# xiqiu.net
KiCad netlist of a schematic drawn in Altium Designer
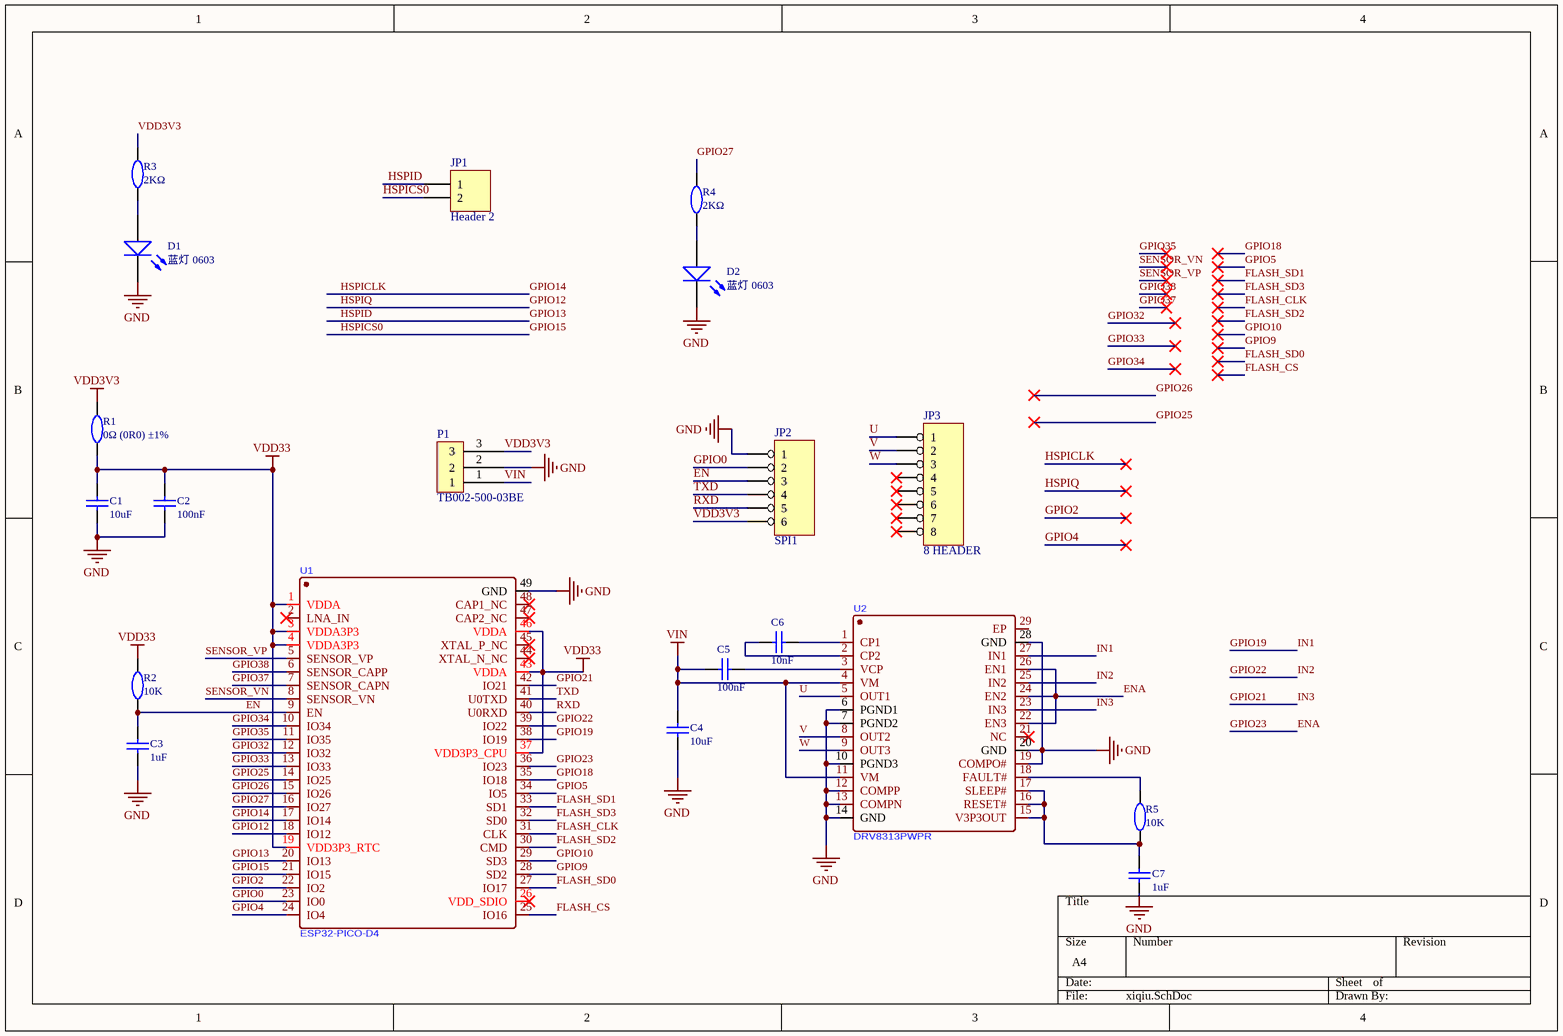
[diagram p0: xiqiu.SchDoc]

(export (version "E")
  (design (tool "Eeschema 10.0.6"))
  (components
    (comp (ref "C1")
      (value "10uF")
      (footprint "0603C")
      (libsource (lib "altium-import") (part "root_1_10uF_"))
    )
    (comp (ref "C2")
      (value "100nF")
      (footprint "0603C")
      (libsource (lib "altium-import") (part "root_1_100nF_"))
    )
    (comp (ref "C3") (value "1uF") (footprint "0603C") (libsource (lib "altium-import") (part "root_1_1uF_")))
    (comp (ref "C4")
      (value "10uF")
      (footprint "0603C")
      (libsource (lib "altium-import") (part "root_1_10uF_"))
    )
    (comp (ref "C5")
      (value "100nF")
      (footprint "0603C")
      (libsource (lib "altium-import") (part "root_2_100nF_"))
    )
    (comp (ref "C6")
      (value "10nF")
      (footprint "0603C")
      (libsource (lib "altium-import") (part "root_0_10nF_"))
    )
    (comp (ref "C7") (value "1uF") (footprint "0603C") (libsource (lib "altium-import") (part "root_1_1uF_")))
    (comp (ref "D1")
      (value "蓝灯 0603")
      (footprint "0603_diode")
      (libsource (lib "altium-import") (part "root_3_蓝灯 0603_"))
    )
    (comp (ref "D2")
      (value "蓝灯 0603")
      (footprint "0603_diode")
      (libsource (lib "altium-import") (part "root_3_蓝灯 0603_"))
    )
    (comp (ref "JP1")
      (value "Header 2")
      (footprint "SHDR2")
      (description "Header, 2-Pin")
      (fields (field (name "PUBLISHER") "Altium Limited"))
      (libsource (lib "Miscellaneous Connectors") (part "Header 2"))
    )
    (comp (ref "JP2") (value "SPI1") (footprint "SHDR6") (libsource (lib "刘涛20200314") (part "HEADER 6")))
    (comp (ref "JP3")
      (value "8 HEADER")
      (footprint "8P - WF25122")
      (description "8 Pin Header")
      (libsource (lib "刘涛20200314") (part "8 HEADER"))
    )
    (comp (ref "P1")
      (value "TB002-500-03BE")
      (footprint "SHDR3")
      (libsource (lib "ArduinoFOC") (part "TB002-500-03BE"))
    )
    (comp (ref "R1")
      (value "0Ω (0R0) ±1%")
      (footprint "0603")
      (libsource (lib "altium-import") (part "root_1_0Ω (0R0) ±1%_"))
    )
    (comp (ref "R2") (value "10K") (footprint "0603R") (libsource (lib "altium-import") (part "root_1_10K_")))
    (comp (ref "R3") (value "2KΩ") (footprint "0603") (libsource (lib "altium-import") (part "root_1_2KΩ_")))
    (comp (ref "R4") (value "2KΩ") (footprint "0603") (libsource (lib "altium-import") (part "root_1_2KΩ_")))
    (comp (ref "R5") (value "10K") (footprint "0603R") (libsource (lib "altium-import") (part "root_1_10K_")))
    (comp (ref "U1")
      (value "ESP32-PICO-D4")
      (footprint "pico")
      (libsource (lib "altium-import") (part "root_0_ESP32-PICO-D4_"))
    )
    (comp (ref "U2")
      (value "DRV8313PWPR")
      (footprint "HTSSOP-28_L9.8-W4.5-P0.65-LS6.6-BL-EP")
      (libsource (lib "altium-import") (part "root_0_DRV8313PWPR_"))
    )
  )
  (nets
    (net (code "1") (name "/EN") (class "Default")
      (node (ref "C3") (pin "2") (pinfunction "2_2") (pintype "passive"))
      (node (ref "JP2") (pin "3") (pinfunction "3_3") (pintype "passive"))
      (node (ref "R2") (pin "1") (pinfunction "1_1") (pintype "passive"))
      (node (ref "U1") (pin "9") (pinfunction "EN_9") (pintype "passive"))
    )
    (net (code "2") (name "/ENA") (class "Default")
      (node (ref "U1") (pin "36") (pinfunction "IO23_36") (pintype "passive"))
      (node (ref "U2") (pin "22") (pinfunction "EN3_22") (pintype "passive"))
      (node (ref "U2") (pin "24") (pinfunction "EN2_24") (pintype "passive"))
      (node (ref "U2") (pin "26") (pinfunction "EN1_26") (pintype "passive"))
    )
    (net (code "3") (name "/FLASH_CLK") (class "Default")
      (node (ref "U1") (pin "31") (pinfunction "CLK_31") (pintype "passive"))
    )
    (net (code "4") (name "/FLASH_CS") (class "Default")
      (node (ref "U1") (pin "25") (pinfunction "IO16_25") (pintype "passive"))
    )
    (net (code "5") (name "/FLASH_SD0") (class "Default")
      (node (ref "U1") (pin "27") (pinfunction "IO17_27") (pintype "passive"))
    )
    (net (code "6") (name "/FLASH_SD1") (class "Default")
      (node (ref "U1") (pin "33") (pinfunction "SD1_33") (pintype "passive"))
    )
    (net (code "7") (name "/FLASH_SD2") (class "Default")
      (node (ref "U1") (pin "30") (pinfunction "CMD_30") (pintype "passive"))
    )
    (net (code "8") (name "/FLASH_SD3") (class "Default")
      (node (ref "U1") (pin "32") (pinfunction "SD0_32") (pintype "passive"))
    )
    (net (code "9") (name "/GPIO0") (class "Default")
      (node (ref "JP2") (pin "2") (pinfunction "2_2") (pintype "passive"))
      (node (ref "U1") (pin "23") (pinfunction "IO0_23") (pintype "passive"))
    )
    (net (code "10") (name "/GPIO2") (class "Default")
      (node (ref "U1") (pin "22") (pinfunction "IO2_22") (pintype "passive"))
    )
    (net (code "11") (name "/GPIO4") (class "Default")
      (node (ref "U1") (pin "24") (pinfunction "IO4_24") (pintype "passive"))
    )
    (net (code "12") (name "/GPIO5") (class "Default")
      (node (ref "U1") (pin "34") (pinfunction "IO5_34") (pintype "passive"))
    )
    (net (code "13") (name "/GPIO9") (class "Default")
      (node (ref "U1") (pin "28") (pinfunction "SD2_28") (pintype "passive"))
    )
    (net (code "14") (name "/GPIO10") (class "Default")
      (node (ref "U1") (pin "29") (pinfunction "SD3_29") (pintype "passive"))
    )
    (net (code "15") (name "/GPIO12") (class "Default")
      (node (ref "U1") (pin "18") (pinfunction "IO12_18") (pintype "passive"))
    )
    (net (code "16") (name "/GPIO13") (class "Default")
      (node (ref "JP1") (pin "2") (pinfunction "1_2") (pintype "passive"))
      (node (ref "U1") (pin "20") (pinfunction "IO13_20") (pintype "passive"))
    )
    (net (code "17") (name "/GPIO14") (class "Default")
      (node (ref "U1") (pin "17") (pinfunction "IO14_17") (pintype "passive"))
    )
    (net (code "18") (name "/GPIO15") (class "Default")
      (node (ref "JP1") (pin "1") (pinfunction "2_1") (pintype "passive"))
      (node (ref "U1") (pin "21") (pinfunction "IO15_21") (pintype "passive"))
    )
    (net (code "19") (name "/GPIO18") (class "Default")
      (node (ref "U1") (pin "35") (pinfunction "IO18_35") (pintype "passive"))
    )
    (net (code "20") (name "/GPIO19") (class "Default")
      (node (ref "U1") (pin "38") (pinfunction "IO19_38") (pintype "passive"))
      (node (ref "U2") (pin "27") (pinfunction "IN1_27") (pintype "passive"))
    )
    (net (code "21") (name "/GPIO21") (class "Default")
      (node (ref "U1") (pin "42") (pinfunction "IO21_42") (pintype "passive"))
      (node (ref "U2") (pin "23") (pinfunction "IN3_23") (pintype "passive"))
    )
    (net (code "22") (name "/GPIO22") (class "Default")
      (node (ref "U1") (pin "39") (pinfunction "IO22_39") (pintype "passive"))
      (node (ref "U2") (pin "25") (pinfunction "IN2_25") (pintype "passive"))
    )
    (net (code "23") (name "/GPIO25") (class "Default")
      (node (ref "U1") (pin "14") (pinfunction "IO25_14") (pintype "passive"))
    )
    (net (code "24") (name "/GPIO26") (class "Default")
      (node (ref "U1") (pin "15") (pinfunction "IO26_15") (pintype "passive"))
    )
    (net (code "25") (name "/GPIO27") (class "Default")
      (node (ref "R4") (pin "2") (pinfunction "2_2") (pintype "passive"))
      (node (ref "U1") (pin "16") (pinfunction "IO27_16") (pintype "passive"))
    )
    (net (code "26") (name "/GPIO32") (class "Default")
      (node (ref "U1") (pin "12") (pinfunction "IO32_12") (pintype "passive"))
    )
    (net (code "27") (name "/GPIO33") (class "Default")
      (node (ref "U1") (pin "13") (pinfunction "IO33_13") (pintype "passive"))
    )
    (net (code "28") (name "/GPIO34") (class "Default")
      (node (ref "U1") (pin "10") (pinfunction "IO34_10") (pintype "passive"))
    )
    (net (code "29") (name "/GPIO35") (class "Default")
      (node (ref "U1") (pin "11") (pinfunction "IO35_11") (pintype "passive"))
    )
    (net (code "30") (name "/GPIO37") (class "Default")
      (node (ref "U1") (pin "7") (pinfunction "SENSOR_CAPN_7") (pintype "passive"))
    )
    (net (code "31") (name "/GPIO38") (class "Default")
      (node (ref "U1") (pin "6") (pinfunction "SENSOR_CAPP_6") (pintype "passive"))
    )
    (net (code "32") (name "/RXD") (class "Default")
      (node (ref "JP2") (pin "5") (pinfunction "5_5") (pintype "passive"))
      (node (ref "U1") (pin "40") (pinfunction "U0RXD_40") (pintype "passive"))
    )
    (net (code "33") (name "/SENSOR_VN") (class "Default")
      (node (ref "U1") (pin "8") (pinfunction "SENSOR_VN_8") (pintype "passive"))
    )
    (net (code "34") (name "/SENSOR_VP") (class "Default")
      (node (ref "U1") (pin "5") (pinfunction "SENSOR_VP_5") (pintype "passive"))
    )
    (net (code "35") (name "/TXD") (class "Default")
      (node (ref "JP2") (pin "4") (pinfunction "4_4") (pintype "passive"))
      (node (ref "U1") (pin "41") (pinfunction "U0TXD_41") (pintype "passive"))
    )
    (net (code "36") (name "/U") (class "Default")
      (node (ref "JP3") (pin "1") (pinfunction "1_1") (pintype "passive"))
      (node (ref "U2") (pin "5") (pinfunction "OUT1_5") (pintype "passive"))
    )
    (net (code "37") (name "/V") (class "Default")
      (node (ref "JP3") (pin "2") (pinfunction "2_2") (pintype "passive"))
      (node (ref "U2") (pin "8") (pinfunction "OUT2_8") (pintype "passive"))
    )
    (net (code "38") (name "/W") (class "Default")
      (node (ref "JP3") (pin "3") (pinfunction "3_3") (pintype "passive"))
      (node (ref "U2") (pin "9") (pinfunction "OUT3_9") (pintype "passive"))
    )
    (net (code "39") (name "GND") (class "Default")
      (node (ref "C1") (pin "1") (pinfunction "1_1") (pintype "passive"))
      (node (ref "C2") (pin "1") (pinfunction "1_1") (pintype "passive"))
      (node (ref "C3") (pin "1") (pinfunction "1_1") (pintype "passive"))
      (node (ref "C4") (pin "1") (pinfunction "1_1") (pintype "passive"))
      (node (ref "C7") (pin "1") (pinfunction "1_1") (pintype "passive"))
      (node (ref "D1") (pin "K") (pinfunction "K_K") (pintype "passive"))
      (node (ref "D2") (pin "K") (pinfunction "K_K") (pintype "passive"))
      (node (ref "JP2") (pin "1") (pinfunction "1_1") (pintype "passive"))
      (node (ref "P1") (pin "2") (pinfunction "2_2") (pintype "passive"))
      (node (ref "U1") (pin "49") (pinfunction "GND_49") (pintype "passive"))
      (node (ref "U2") (pin "10") (pinfunction "PGND3_10") (pintype "passive"))
      (node (ref "U2") (pin "12") (pinfunction "COMPP_12") (pintype "passive"))
      (node (ref "U2") (pin "13") (pinfunction "COMPN_13") (pintype "passive"))
      (node (ref "U2") (pin "14") (pinfunction "GND_14") (pintype "passive"))
      (node (ref "U2") (pin "19") (pinfunction "COMPO#_19") (pintype "passive"))
      (node (ref "U2") (pin "20") (pinfunction "GND_20") (pintype "passive"))
      (node (ref "U2") (pin "28") (pinfunction "GND_28") (pintype "passive"))
      (node (ref "U2") (pin "6") (pinfunction "PGND1_6") (pintype "passive"))
      (node (ref "U2") (pin "7") (pinfunction "PGND2_7") (pintype "passive"))
    )
    (net (code "40") (name "Net-(D1-PadA)") (class "Default")
      (node (ref "D1") (pin "A") (pinfunction "A_A") (pintype "passive"))
      (node (ref "R3") (pin "1") (pinfunction "1_1") (pintype "passive"))
    )
    (net (code "41") (name "Net-(D2-PadA)") (class "Default")
      (node (ref "D2") (pin "A") (pinfunction "A_A") (pintype "passive"))
      (node (ref "R4") (pin "1") (pinfunction "1_1") (pintype "passive"))
    )
    (net (code "42") (name "Net-(U2-CP1)") (class "Default")
      (node (ref "C6") (pin "2") (pinfunction "2_2") (pintype "passive"))
      (node (ref "U2") (pin "1") (pinfunction "CP1_1") (pintype "passive"))
    )
    (net (code "43") (name "Net-(U2-CP2)") (class "Default")
      (node (ref "C6") (pin "1") (pinfunction "1_1") (pintype "passive"))
      (node (ref "U2") (pin "2") (pinfunction "CP2_2") (pintype "passive"))
    )
    (net (code "44") (name "Net-(U2-FAULT#)") (class "Default")
      (node (ref "R5") (pin "2") (pinfunction "2_2") (pintype "passive"))
      (node (ref "U2") (pin "18") (pinfunction "FAULT#_18") (pintype "passive"))
    )
    (net (code "45") (name "Net-(U2-RESET#)") (class "Default")
      (node (ref "C7") (pin "2") (pinfunction "2_2") (pintype "passive"))
      (node (ref "R5") (pin "1") (pinfunction "1_1") (pintype "passive"))
      (node (ref "U2") (pin "15") (pinfunction "V3P3OUT_15") (pintype "passive"))
      (node (ref "U2") (pin "16") (pinfunction "RESET#_16") (pintype "passive"))
      (node (ref "U2") (pin "17") (pinfunction "SLEEP#_17") (pintype "passive"))
    )
    (net (code "46") (name "Net-(U2-VCP)") (class "Default")
      (node (ref "C5") (pin "1") (pinfunction "1_1") (pintype "passive"))
      (node (ref "U2") (pin "3") (pinfunction "VCP_3") (pintype "passive"))
    )
    (net (code "47") (name "VDD3V3") (class "Default")
      (node (ref "JP2") (pin "6") (pinfunction "6_6") (pintype "passive"))
      (node (ref "P1") (pin "3") (pinfunction "3_3") (pintype "passive"))
      (node (ref "R1") (pin "2") (pinfunction "2_2") (pintype "passive"))
      (node (ref "R3") (pin "2") (pinfunction "2_2") (pintype "passive"))
    )
    (net (code "48") (name "VDD33") (class "Default")
      (node (ref "C1") (pin "2") (pinfunction "2_2") (pintype "passive"))
      (node (ref "C2") (pin "2") (pinfunction "2_2") (pintype "passive"))
      (node (ref "R1") (pin "1") (pinfunction "1_1") (pintype "passive"))
      (node (ref "R2") (pin "2") (pinfunction "2_2") (pintype "passive"))
      (node (ref "U1") (pin "1") (pinfunction "VDDA_1") (pintype "passive"))
      (node (ref "U1") (pin "19") (pinfunction "VDD3P3_RTC_19") (pintype "passive"))
      (node (ref "U1") (pin "3") (pinfunction "VDDA3P3_3") (pintype "passive"))
      (node (ref "U1") (pin "37") (pinfunction "VDD3P3_CPU_37") (pintype "passive"))
      (node (ref "U1") (pin "4") (pinfunction "VDDA3P3_4") (pintype "passive"))
      (node (ref "U1") (pin "43") (pinfunction "VDDA_43") (pintype "passive"))
      (node (ref "U1") (pin "46") (pinfunction "VDDA_46") (pintype "passive"))
    )
    (net (code "49") (name "VIN") (class "Default")
      (node (ref "C4") (pin "2") (pinfunction "2_2") (pintype "passive"))
      (node (ref "C5") (pin "2") (pinfunction "2_2") (pintype "passive"))
      (node (ref "P1") (pin "1") (pinfunction "1_1") (pintype "passive"))
      (node (ref "U2") (pin "11") (pinfunction "VM_11") (pintype "passive"))
      (node (ref "U2") (pin "4") (pinfunction "VM_4") (pintype "passive"))
    )
    (net (code "50") (name "unconnected-(JP3-Pad4)") (class "Default")
      (node (ref "JP3") (pin "4") (pinfunction "4_4") (pintype "passive+no_connect"))
    )
    (net (code "51") (name "unconnected-(JP3-Pad5)") (class "Default")
      (node (ref "JP3") (pin "5") (pinfunction "5_5") (pintype "passive+no_connect"))
    )
    (net (code "52") (name "unconnected-(JP3-Pad6)") (class "Default")
      (node (ref "JP3") (pin "6") (pinfunction "6_6") (pintype "passive+no_connect"))
    )
    (net (code "53") (name "unconnected-(JP3-Pad7)") (class "Default")
      (node (ref "JP3") (pin "7") (pinfunction "7_7") (pintype "passive+no_connect"))
    )
    (net (code "54") (name "unconnected-(JP3-Pad8)") (class "Default")
      (node (ref "JP3") (pin "8") (pinfunction "8_8") (pintype "passive+no_connect"))
    )
    (net (code "55") (name "unconnected-(U1-CAP1_NC-Pad48)") (class "Default")
      (node (ref "U1") (pin "48") (pinfunction "CAP1_NC_48") (pintype "passive+no_connect"))
    )
    (net (code "56") (name "unconnected-(U1-CAP2_NC-Pad47)") (class "Default")
      (node (ref "U1") (pin "47") (pinfunction "CAP2_NC_47") (pintype "passive+no_connect"))
    )
    (net (code "57") (name "unconnected-(U1-LNA_IN-Pad2)") (class "Default")
      (node (ref "U1") (pin "2") (pinfunction "LNA_IN_2") (pintype "passive+no_connect"))
    )
    (net (code "58") (name "unconnected-(U1-VDD_SDIO-Pad26)") (class "Default")
      (node (ref "U1") (pin "26") (pinfunction "VDD_SDIO_26") (pintype "passive+no_connect"))
    )
    (net (code "59") (name "unconnected-(U1-XTAL_N_NC-Pad44)") (class "Default")
      (node (ref "U1") (pin "44") (pinfunction "XTAL_N_NC_44") (pintype "passive+no_connect"))
    )
    (net (code "60") (name "unconnected-(U1-XTAL_P_NC-Pad45)") (class "Default")
      (node (ref "U1") (pin "45") (pinfunction "XTAL_P_NC_45") (pintype "passive+no_connect"))
    )
    (net (code "61") (name "unconnected-(U2-EP-Pad29)") (class "Default")
      (node (ref "U2") (pin "29") (pinfunction "EP_29") (pintype "passive"))
    )
    (net (code "62") (name "unconnected-(U2-NC-Pad21)") (class "Default")
      (node (ref "U2") (pin "21") (pinfunction "NC_21") (pintype "passive+no_connect"))
    )
  )
)
